# TPcape_breakout.net
KiCad netlist of a schematic drawn in Altium Designer
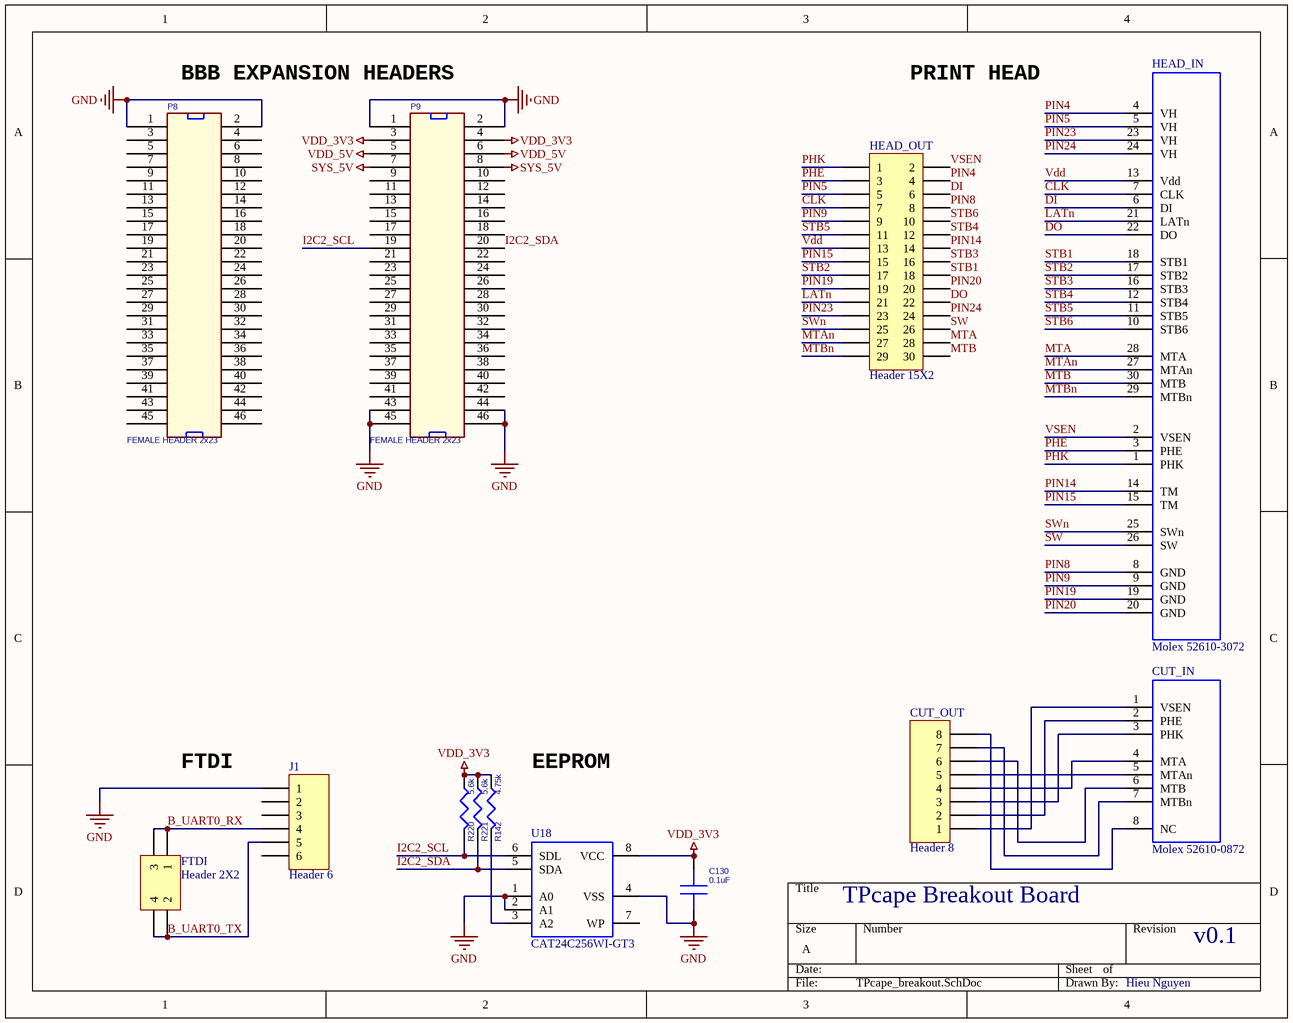
[diagram p0: TPcape_breakout.SchDoc]

(export (version "E")
  (design (tool "Eeschema 10.0.6"))
  (components
    (comp (ref "C130")
      (value "0.1uF")
      (footprint "402")
      (description "No Description")
      (libsource (lib "BEAGLEBONEBLACK_REV A5B") (part "CAP SMD"))
    )
    (comp (ref "CUT_IN")
      (value "Molex 52610-0872")
      (footprint "Molex 52610-0872")
      (description "FPC connector for Fujitsu FTP-628MCL401 (Molex 52610-0871 is obsolete)")
      (libsource (lib "AM335x_Thermal_Printer") (part "Molex 52610-0872"))
    )
    (comp (ref "CUT_OUT")
      (value "Header 8")
      (footprint "HDR1X8")
      (description "Header, 8-Pin")
      (fields (field (name "PUBLISHER") "Altium Limited"))
      (libsource (lib "Miscellaneous Connectors") (part "Header 8"))
    )
    (comp (ref "FTDI")
      (value "Header 2X2")
      (footprint "SSM-102-S-DV")
      (description "Header, 2-Pin, Dual row")
      (fields (field (name "PUBLISHER") "Altium Limited"))
      (libsource (lib "Miscellaneous Connectors") (part "Header 2X2"))
    )
    (comp (ref "HEAD_IN")
      (value "Molex 52610-3072")
      (footprint "Molex 52610-3072")
      (description "FPC connector for Fujitsu FTP-628MCL401 print head (Molex 52610-3071 is obsolete)")
      (libsource (lib "AM335x_Thermal_Printer") (part "Molex 52610-3072"))
    )
    (comp (ref "HEAD_OUT")
      (value "Header 15X2")
      (footprint "HDR2X15")
      (description "Header, 15-Pin, Dual row")
      (fields (field (name "PUBLISHER") "Altium Limited"))
      (libsource (lib "Miscellaneous Connectors") (part "Header 15X2"))
    )
    (comp (ref "J1")
      (value "Header 6")
      (footprint "HDR1X6")
      (description "Header, 6-Pin")
      (fields (field (name "PUBLISHER") "Altium Limited"))
      (libsource (lib "Miscellaneous Connectors") (part "Header 6"))
    )
    (comp (ref "P8")
      (value "FEMALE HEADER 2x23")
      (description "CONN HEADER FMAL 46PS.1\" DL GOLD")
      (fields
        (field (name "MANUFACTURER") "Sullins Connector Solutions")
        (field (name "MANUFACTURER PART NUMBER") "PPPC232LFBN-RC")
      )
      (libsource (lib "BEAGLEBONEBLACK_REV A5B") (part "HDR_46_F_2_0.1_0.1"))
    )
    (comp (ref "P9")
      (value "FEMALE HEADER 2x23")
      (description "CONN HEADER FMAL 46PS.1\" DL GOLD")
      (fields
        (field (name "MANUFACTURER") "Sullins Connector Solutions")
        (field (name "MANUFACTURER PART NUMBER") "PPPC232LFBN-RC")
      )
      (libsource (lib "BEAGLEBONEBLACK_REV A5B") (part "HDR_46_F_2_0.1_0.1"))
    )
    (comp (ref "R142")
      (value "4.75k")
      (footprint "402")
      (description "RES 5.6K OHM 1/16W 5% 0402 SMD")
      (fields
        (field (name "MANUFACTURER") "Rohm Semiconductor")
        (field (name "MANUFACTURER PART NUMBER") "MCR01MZPJ103")
      )
      (libsource (lib "BEAGLEBONEBLACK_REV A5B") (part "RES SMD"))
    )
    (comp (ref "R220")
      (value "5.6k")
      (footprint "402")
      (description "RES 5.6K OHM 1/16W 5% 0402 SMD")
      (fields
        (field (name "MANUFACTURER") "Rohm Semiconductor")
        (field (name "MANUFACTURER PART NUMBER") "MCR01MZPJ103")
      )
      (libsource (lib "BEAGLEBONEBLACK_REV A5B") (part "RES SMD"))
    )
    (comp (ref "R221")
      (value "5.6k")
      (footprint "402")
      (description "RES 5.6K OHM 1/16W 5% 0402 SMD")
      (fields
        (field (name "MANUFACTURER") "Rohm Semiconductor")
        (field (name "MANUFACTURER PART NUMBER") "MCR01MZPJ103")
      )
      (libsource (lib "BEAGLEBONEBLACK_REV A5B") (part "RES SMD"))
    )
    (comp (ref "U18")
      (value "CAT24C256WI-GT3")
      (footprint "CAT24C256WI-GT3")
      (description "IC EEPROM 256KBIT 400KHZ 8SOIC")
      (libsource (lib "AM335x_Thermal_Printer") (part "CAT24C256WI-GT3"))
    )
  )
  (nets
    (net (code "1") (name "/B_UART0_RX") (class "Default")
      (node (ref "FTDI") (pin "1") (pinfunction "1_1") (pintype "passive"))
      (node (ref "FTDI") (pin "3") (pinfunction "3_3") (pintype "passive"))
      (node (ref "J1") (pin "4") (pinfunction "4_4") (pintype "passive"))
    )
    (net (code "2") (name "/B_UART0_TX") (class "Default")
      (node (ref "FTDI") (pin "2") (pinfunction "2_2") (pintype "passive"))
      (node (ref "FTDI") (pin "4") (pinfunction "4_4") (pintype "passive"))
      (node (ref "J1") (pin "5") (pinfunction "5_5") (pintype "passive"))
    )
    (net (code "3") (name "/CLK") (class "Default")
      (node (ref "HEAD_IN") (pin "7") (pinfunction "CLK_7") (pintype "passive"))
      (node (ref "HEAD_OUT") (pin "7") (pinfunction "7_7") (pintype "passive"))
    )
    (net (code "4") (name "/DI") (class "Default")
      (node (ref "HEAD_IN") (pin "6") (pinfunction "DI_6") (pintype "passive"))
      (node (ref "HEAD_OUT") (pin "6") (pinfunction "6_6") (pintype "passive"))
    )
    (net (code "5") (name "/DO") (class "Default")
      (node (ref "HEAD_IN") (pin "22") (pinfunction "DO_22") (pintype "passive"))
      (node (ref "HEAD_OUT") (pin "22") (pinfunction "22_22") (pintype "passive"))
    )
    (net (code "6") (name "/I2C2_SCL") (class "Default")
      (node (ref "P9") (pin "19") (pinfunction "10_19") (pintype "passive"))
      (node (ref "R220") (pin "1") (pinfunction "P1_1") (pintype "passive"))
      (node (ref "U18") (pin "6") (pinfunction "SDL_6") (pintype "passive"))
    )
    (net (code "7") (name "/I2C2_SDA") (class "Default")
      (node (ref "P9") (pin "20") (pinfunction "35_20") (pintype "passive"))
      (node (ref "R221") (pin "1") (pinfunction "P1_1") (pintype "passive"))
      (node (ref "U18") (pin "5") (pinfunction "SDA_5") (pintype "passive"))
    )
    (net (code "8") (name "/LATn") (class "Default")
      (node (ref "HEAD_IN") (pin "21") (pinfunction "LATn_21") (pintype "passive"))
      (node (ref "HEAD_OUT") (pin "21") (pinfunction "21_21") (pintype "passive"))
    )
    (net (code "9") (name "/MTA") (class "Default")
      (node (ref "HEAD_IN") (pin "28") (pinfunction "MTA_28") (pintype "passive"))
      (node (ref "HEAD_OUT") (pin "28") (pinfunction "28_28") (pintype "passive"))
    )
    (net (code "10") (name "/MTAn") (class "Default")
      (node (ref "HEAD_IN") (pin "27") (pinfunction "MTAn_27") (pintype "passive"))
      (node (ref "HEAD_OUT") (pin "27") (pinfunction "27_27") (pintype "passive"))
    )
    (net (code "11") (name "/MTB") (class "Default")
      (node (ref "HEAD_IN") (pin "30") (pinfunction "MTB_30") (pintype "passive"))
      (node (ref "HEAD_OUT") (pin "30") (pinfunction "30_30") (pintype "passive"))
    )
    (net (code "12") (name "/MTBn") (class "Default")
      (node (ref "HEAD_IN") (pin "29") (pinfunction "MTBn_29") (pintype "passive"))
      (node (ref "HEAD_OUT") (pin "29") (pinfunction "29_29") (pintype "passive"))
    )
    (net (code "13") (name "/PHE") (class "Default")
      (node (ref "HEAD_IN") (pin "3") (pinfunction "PHE_3") (pintype "passive"))
      (node (ref "HEAD_OUT") (pin "3") (pinfunction "3_3") (pintype "passive"))
    )
    (net (code "14") (name "/PHK") (class "Default")
      (node (ref "HEAD_IN") (pin "1") (pinfunction "PHK_1") (pintype "passive"))
      (node (ref "HEAD_OUT") (pin "1") (pinfunction "1_1") (pintype "passive"))
    )
    (net (code "15") (name "/PIN4") (class "Default")
      (node (ref "HEAD_IN") (pin "4") (pinfunction "VH_4") (pintype "passive"))
      (node (ref "HEAD_OUT") (pin "4") (pinfunction "4_4") (pintype "passive"))
    )
    (net (code "16") (name "/PIN5") (class "Default")
      (node (ref "HEAD_IN") (pin "5") (pinfunction "VH_5") (pintype "passive"))
      (node (ref "HEAD_OUT") (pin "5") (pinfunction "5_5") (pintype "passive"))
    )
    (net (code "17") (name "/PIN8") (class "Default")
      (node (ref "HEAD_IN") (pin "8") (pinfunction "GND_8") (pintype "passive"))
      (node (ref "HEAD_OUT") (pin "8") (pinfunction "8_8") (pintype "passive"))
    )
    (net (code "18") (name "/PIN9") (class "Default")
      (node (ref "HEAD_IN") (pin "9") (pinfunction "GND_9") (pintype "passive"))
      (node (ref "HEAD_OUT") (pin "9") (pinfunction "9_9") (pintype "passive"))
    )
    (net (code "19") (name "/PIN14") (class "Default")
      (node (ref "HEAD_IN") (pin "14") (pinfunction "TM_14") (pintype "passive"))
      (node (ref "HEAD_OUT") (pin "14") (pinfunction "14_14") (pintype "passive"))
    )
    (net (code "20") (name "/PIN15") (class "Default")
      (node (ref "HEAD_IN") (pin "15") (pinfunction "TM_15") (pintype "passive"))
      (node (ref "HEAD_OUT") (pin "15") (pinfunction "15_15") (pintype "passive"))
    )
    (net (code "21") (name "/PIN19") (class "Default")
      (node (ref "HEAD_IN") (pin "19") (pinfunction "GND_19") (pintype "passive"))
      (node (ref "HEAD_OUT") (pin "19") (pinfunction "19_19") (pintype "passive"))
    )
    (net (code "22") (name "/PIN20") (class "Default")
      (node (ref "HEAD_IN") (pin "20") (pinfunction "GND_20") (pintype "passive"))
      (node (ref "HEAD_OUT") (pin "20") (pinfunction "20_20") (pintype "passive"))
    )
    (net (code "23") (name "/PIN23") (class "Default")
      (node (ref "HEAD_IN") (pin "23") (pinfunction "VH_23") (pintype "passive"))
      (node (ref "HEAD_OUT") (pin "23") (pinfunction "23_23") (pintype "passive"))
    )
    (net (code "24") (name "/PIN24") (class "Default")
      (node (ref "HEAD_IN") (pin "24") (pinfunction "VH_24") (pintype "passive"))
      (node (ref "HEAD_OUT") (pin "24") (pinfunction "24_24") (pintype "passive"))
    )
    (net (code "25") (name "/STB1") (class "Default")
      (node (ref "HEAD_IN") (pin "18") (pinfunction "STB1_18") (pintype "passive"))
      (node (ref "HEAD_OUT") (pin "18") (pinfunction "18_18") (pintype "passive"))
    )
    (net (code "26") (name "/STB2") (class "Default")
      (node (ref "HEAD_IN") (pin "17") (pinfunction "STB2_17") (pintype "passive"))
      (node (ref "HEAD_OUT") (pin "17") (pinfunction "17_17") (pintype "passive"))
    )
    (net (code "27") (name "/STB3") (class "Default")
      (node (ref "HEAD_IN") (pin "16") (pinfunction "STB3_16") (pintype "passive"))
      (node (ref "HEAD_OUT") (pin "16") (pinfunction "16_16") (pintype "passive"))
    )
    (net (code "28") (name "/STB4") (class "Default")
      (node (ref "HEAD_IN") (pin "12") (pinfunction "STB4_12") (pintype "passive"))
      (node (ref "HEAD_OUT") (pin "12") (pinfunction "12_12") (pintype "passive"))
    )
    (net (code "29") (name "/STB5") (class "Default")
      (node (ref "HEAD_IN") (pin "11") (pinfunction "STB5_11") (pintype "passive"))
      (node (ref "HEAD_OUT") (pin "11") (pinfunction "11_11") (pintype "passive"))
    )
    (net (code "30") (name "/STB6") (class "Default")
      (node (ref "HEAD_IN") (pin "10") (pinfunction "STB6_10") (pintype "passive"))
      (node (ref "HEAD_OUT") (pin "10") (pinfunction "10_10") (pintype "passive"))
    )
    (net (code "31") (name "/SW") (class "Default")
      (node (ref "HEAD_IN") (pin "26") (pinfunction "SW_26") (pintype "passive"))
      (node (ref "HEAD_OUT") (pin "26") (pinfunction "26_26") (pintype "passive"))
    )
    (net (code "32") (name "/SWn") (class "Default")
      (node (ref "HEAD_IN") (pin "25") (pinfunction "SWn_25") (pintype "passive"))
      (node (ref "HEAD_OUT") (pin "25") (pinfunction "25_25") (pintype "passive"))
    )
    (net (code "33") (name "/VSEN") (class "Default")
      (node (ref "HEAD_IN") (pin "2") (pinfunction "VSEN_2") (pintype "passive"))
      (node (ref "HEAD_OUT") (pin "2") (pinfunction "2_2") (pintype "passive"))
    )
    (net (code "34") (name "/Vdd") (class "Default")
      (node (ref "HEAD_IN") (pin "13") (pinfunction "Vdd_13") (pintype "passive"))
      (node (ref "HEAD_OUT") (pin "13") (pinfunction "13_13") (pintype "passive"))
    )
    (net (code "35") (name "GND") (class "Default")
      (node (ref "C130") (pin "2") (pinfunction "2_2") (pintype "passive"))
      (node (ref "J1") (pin "1") (pinfunction "1_1") (pintype "passive"))
      (node (ref "P8") (pin "1") (pinfunction "1_1") (pintype "passive"))
      (node (ref "P8") (pin "2") (pinfunction "26_2") (pintype "passive"))
      (node (ref "P9") (pin "1") (pinfunction "1_1") (pintype "passive"))
      (node (ref "P9") (pin "2") (pinfunction "26_2") (pintype "passive"))
      (node (ref "P9") (pin "43") (pinfunction "22_43") (pintype "passive"))
      (node (ref "P9") (pin "44") (pinfunction "47_44") (pintype "passive"))
      (node (ref "P9") (pin "45") (pinfunction "23_45") (pintype "passive"))
      (node (ref "P9") (pin "46") (pinfunction "48_46") (pintype "passive"))
      (node (ref "U18") (pin "1") (pinfunction "A0_1") (pintype "passive"))
      (node (ref "U18") (pin "2") (pinfunction "A1_2") (pintype "passive"))
      (node (ref "U18") (pin "4") (pinfunction "VSS_4") (pintype "passive"))
    )
    (net (code "36") (name "Net-(CUT_IN-MTA)") (class "Default")
      (node (ref "CUT_IN") (pin "4") (pinfunction "MTA_4") (pintype "passive"))
      (node (ref "CUT_OUT") (pin "4") (pinfunction "4_4") (pintype "passive"))
    )
    (net (code "37") (name "Net-(CUT_IN-MTAn)") (class "Default")
      (node (ref "CUT_IN") (pin "5") (pinfunction "MTAn_5") (pintype "passive"))
      (node (ref "CUT_OUT") (pin "5") (pinfunction "5_5") (pintype "passive"))
    )
    (net (code "38") (name "Net-(CUT_IN-MTB)") (class "Default")
      (node (ref "CUT_IN") (pin "6") (pinfunction "MTB_6") (pintype "passive"))
      (node (ref "CUT_OUT") (pin "6") (pinfunction "6_6") (pintype "passive"))
    )
    (net (code "39") (name "Net-(CUT_IN-MTBn)") (class "Default")
      (node (ref "CUT_IN") (pin "7") (pinfunction "MTBn_7") (pintype "passive"))
      (node (ref "CUT_OUT") (pin "7") (pinfunction "7_7") (pintype "passive"))
    )
    (net (code "40") (name "Net-(CUT_IN-NC)") (class "Default")
      (node (ref "CUT_IN") (pin "8") (pinfunction "NC_8") (pintype "passive"))
      (node (ref "CUT_OUT") (pin "8") (pinfunction "8_8") (pintype "passive"))
    )
    (net (code "41") (name "Net-(CUT_IN-PHE)") (class "Default")
      (node (ref "CUT_IN") (pin "2") (pinfunction "PHE_2") (pintype "passive"))
      (node (ref "CUT_OUT") (pin "2") (pinfunction "2_2") (pintype "passive"))
    )
    (net (code "42") (name "Net-(CUT_IN-PHK)") (class "Default")
      (node (ref "CUT_IN") (pin "3") (pinfunction "PHK_3") (pintype "passive"))
      (node (ref "CUT_OUT") (pin "3") (pinfunction "3_3") (pintype "passive"))
    )
    (net (code "43") (name "Net-(CUT_IN-VSEN)") (class "Default")
      (node (ref "CUT_IN") (pin "1") (pinfunction "VSEN_1") (pintype "passive"))
      (node (ref "CUT_OUT") (pin "1") (pinfunction "1_1") (pintype "passive"))
    )
    (net (code "44") (name "Net-(R142-P1)") (class "Default")
      (node (ref "R142") (pin "1") (pinfunction "P1_1") (pintype "passive"))
      (node (ref "U18") (pin "3") (pinfunction "A2_3") (pintype "passive"))
    )
    (net (code "45") (name "SYS_5V") (class "Default")
      (node (ref "P9") (pin "7") (pinfunction "4_7") (pintype "passive"))
      (node (ref "P9") (pin "8") (pinfunction "29_8") (pintype "passive"))
    )
    (net (code "46") (name "VDD_3V3") (class "Default")
      (node (ref "C130") (pin "1") (pinfunction "1_1") (pintype "passive"))
      (node (ref "P9") (pin "3") (pinfunction "2_3") (pintype "passive"))
      (node (ref "P9") (pin "4") (pinfunction "27_4") (pintype "passive"))
      (node (ref "R142") (pin "2") (pinfunction "P2_2") (pintype "passive"))
      (node (ref "R220") (pin "2") (pinfunction "P2_2") (pintype "passive"))
      (node (ref "R221") (pin "2") (pinfunction "P2_2") (pintype "passive"))
      (node (ref "U18") (pin "8") (pinfunction "VCC_8") (pintype "passive"))
    )
    (net (code "47") (name "VDD_5V") (class "Default")
      (node (ref "P9") (pin "5") (pinfunction "3_5") (pintype "passive"))
      (node (ref "P9") (pin "6") (pinfunction "28_6") (pintype "passive"))
    )
    (net (code "48") (name "unconnected-(J1-Pad2)") (class "Default")
      (node (ref "J1") (pin "2") (pinfunction "2_2") (pintype "passive"))
    )
    (net (code "49") (name "unconnected-(J1-Pad3)") (class "Default")
      (node (ref "J1") (pin "3") (pinfunction "3_3") (pintype "passive"))
    )
    (net (code "50") (name "unconnected-(J1-Pad6)") (class "Default")
      (node (ref "J1") (pin "6") (pinfunction "6_6") (pintype "passive"))
    )
    (net (code "51") (name "unconnected-(P8-2-Pad3)") (class "Default")
      (node (ref "P8") (pin "3") (pinfunction "2_3") (pintype "passive"))
    )
    (net (code "52") (name "unconnected-(P8-3-Pad5)") (class "Default")
      (node (ref "P8") (pin "5") (pinfunction "3_5") (pintype "passive"))
    )
    (net (code "53") (name "unconnected-(P8-4-Pad7)") (class "Default")
      (node (ref "P8") (pin "7") (pinfunction "4_7") (pintype "passive"))
    )
    (net (code "54") (name "unconnected-(P8-5-Pad9)") (class "Default")
      (node (ref "P8") (pin "9") (pinfunction "5_9") (pintype "passive"))
    )
    (net (code "55") (name "unconnected-(P8-6-Pad11)") (class "Default")
      (node (ref "P8") (pin "11") (pinfunction "6_11") (pintype "passive"))
    )
    (net (code "56") (name "unconnected-(P8-7-Pad13)") (class "Default")
      (node (ref "P8") (pin "13") (pinfunction "7_13") (pintype "passive"))
    )
    (net (code "57") (name "unconnected-(P8-8-Pad15)") (class "Default")
      (node (ref "P8") (pin "15") (pinfunction "8_15") (pintype "passive"))
    )
    (net (code "58") (name "unconnected-(P8-9-Pad17)") (class "Default")
      (node (ref "P8") (pin "17") (pinfunction "9_17") (pintype "passive"))
    )
    (net (code "59") (name "unconnected-(P8-10-Pad19)") (class "Default")
      (node (ref "P8") (pin "19") (pinfunction "10_19") (pintype "passive"))
    )
    (net (code "60") (name "unconnected-(P8-11-Pad21)") (class "Default")
      (node (ref "P8") (pin "21") (pinfunction "11_21") (pintype "passive"))
    )
    (net (code "61") (name "unconnected-(P8-12-Pad23)") (class "Default")
      (node (ref "P8") (pin "23") (pinfunction "12_23") (pintype "passive"))
    )
    (net (code "62") (name "unconnected-(P8-13-Pad25)") (class "Default")
      (node (ref "P8") (pin "25") (pinfunction "13_25") (pintype "passive"))
    )
    (net (code "63") (name "unconnected-(P8-14-Pad27)") (class "Default")
      (node (ref "P8") (pin "27") (pinfunction "14_27") (pintype "passive"))
    )
    (net (code "64") (name "unconnected-(P8-15-Pad29)") (class "Default")
      (node (ref "P8") (pin "29") (pinfunction "15_29") (pintype "passive"))
    )
    (net (code "65") (name "unconnected-(P8-16-Pad31)") (class "Default")
      (node (ref "P8") (pin "31") (pinfunction "16_31") (pintype "passive"))
    )
    (net (code "66") (name "unconnected-(P8-17-Pad33)") (class "Default")
      (node (ref "P8") (pin "33") (pinfunction "17_33") (pintype "passive"))
    )
    (net (code "67") (name "unconnected-(P8-18-Pad35)") (class "Default")
      (node (ref "P8") (pin "35") (pinfunction "18_35") (pintype "passive"))
    )
    (net (code "68") (name "unconnected-(P8-19-Pad37)") (class "Default")
      (node (ref "P8") (pin "37") (pinfunction "19_37") (pintype "passive"))
    )
    (net (code "69") (name "unconnected-(P8-20-Pad39)") (class "Default")
      (node (ref "P8") (pin "39") (pinfunction "20_39") (pintype "passive"))
    )
    (net (code "70") (name "unconnected-(P8-21-Pad41)") (class "Default")
      (node (ref "P8") (pin "41") (pinfunction "21_41") (pintype "passive"))
    )
    (net (code "71") (name "unconnected-(P8-22-Pad43)") (class "Default")
      (node (ref "P8") (pin "43") (pinfunction "22_43") (pintype "passive"))
    )
    (net (code "72") (name "unconnected-(P8-23-Pad45)") (class "Default")
      (node (ref "P8") (pin "45") (pinfunction "23_45") (pintype "passive"))
    )
    (net (code "73") (name "unconnected-(P8-27-Pad4)") (class "Default")
      (node (ref "P8") (pin "4") (pinfunction "27_4") (pintype "passive"))
    )
    (net (code "74") (name "unconnected-(P8-28-Pad6)") (class "Default")
      (node (ref "P8") (pin "6") (pinfunction "28_6") (pintype "passive"))
    )
    (net (code "75") (name "unconnected-(P8-29-Pad8)") (class "Default")
      (node (ref "P8") (pin "8") (pinfunction "29_8") (pintype "passive"))
    )
    (net (code "76") (name "unconnected-(P8-30-Pad10)") (class "Default")
      (node (ref "P8") (pin "10") (pinfunction "30_10") (pintype "passive"))
    )
    (net (code "77") (name "unconnected-(P8-31-Pad12)") (class "Default")
      (node (ref "P8") (pin "12") (pinfunction "31_12") (pintype "passive"))
    )
    (net (code "78") (name "unconnected-(P8-32-Pad14)") (class "Default")
      (node (ref "P8") (pin "14") (pinfunction "32_14") (pintype "passive"))
    )
    (net (code "79") (name "unconnected-(P8-33-Pad16)") (class "Default")
      (node (ref "P8") (pin "16") (pinfunction "33_16") (pintype "passive"))
    )
    (net (code "80") (name "unconnected-(P8-34-Pad18)") (class "Default")
      (node (ref "P8") (pin "18") (pinfunction "34_18") (pintype "passive"))
    )
    (net (code "81") (name "unconnected-(P8-35-Pad20)") (class "Default")
      (node (ref "P8") (pin "20") (pinfunction "35_20") (pintype "passive"))
    )
    (net (code "82") (name "unconnected-(P8-36-Pad22)") (class "Default")
      (node (ref "P8") (pin "22") (pinfunction "36_22") (pintype "passive"))
    )
    (net (code "83") (name "unconnected-(P8-37-Pad24)") (class "Default")
      (node (ref "P8") (pin "24") (pinfunction "37_24") (pintype "passive"))
    )
    (net (code "84") (name "unconnected-(P8-38-Pad26)") (class "Default")
      (node (ref "P8") (pin "26") (pinfunction "38_26") (pintype "passive"))
    )
    (net (code "85") (name "unconnected-(P8-39-Pad28)") (class "Default")
      (node (ref "P8") (pin "28") (pinfunction "39_28") (pintype "passive"))
    )
    (net (code "86") (name "unconnected-(P8-40-Pad30)") (class "Default")
      (node (ref "P8") (pin "30") (pinfunction "40_30") (pintype "passive"))
    )
    (net (code "87") (name "unconnected-(P8-41-Pad32)") (class "Default")
      (node (ref "P8") (pin "32") (pinfunction "41_32") (pintype "passive"))
    )
    (net (code "88") (name "unconnected-(P8-42-Pad34)") (class "Default")
      (node (ref "P8") (pin "34") (pinfunction "42_34") (pintype "passive"))
    )
    (net (code "89") (name "unconnected-(P8-43-Pad36)") (class "Default")
      (node (ref "P8") (pin "36") (pinfunction "43_36") (pintype "passive"))
    )
    (net (code "90") (name "unconnected-(P8-44-Pad38)") (class "Default")
      (node (ref "P8") (pin "38") (pinfunction "44_38") (pintype "passive"))
    )
    (net (code "91") (name "unconnected-(P8-45-Pad40)") (class "Default")
      (node (ref "P8") (pin "40") (pinfunction "45_40") (pintype "passive"))
    )
    (net (code "92") (name "unconnected-(P8-46-Pad42)") (class "Default")
      (node (ref "P8") (pin "42") (pinfunction "46_42") (pintype "passive"))
    )
    (net (code "93") (name "unconnected-(P8-47-Pad44)") (class "Default")
      (node (ref "P8") (pin "44") (pinfunction "47_44") (pintype "passive"))
    )
    (net (code "94") (name "unconnected-(P8-48-Pad46)") (class "Default")
      (node (ref "P8") (pin "46") (pinfunction "48_46") (pintype "passive"))
    )
    (net (code "95") (name "unconnected-(P9-5-Pad9)") (class "Default")
      (node (ref "P9") (pin "9") (pinfunction "5_9") (pintype "passive"))
    )
    (net (code "96") (name "unconnected-(P9-6-Pad11)") (class "Default")
      (node (ref "P9") (pin "11") (pinfunction "6_11") (pintype "passive"))
    )
    (net (code "97") (name "unconnected-(P9-7-Pad13)") (class "Default")
      (node (ref "P9") (pin "13") (pinfunction "7_13") (pintype "passive"))
    )
    (net (code "98") (name "unconnected-(P9-8-Pad15)") (class "Default")
      (node (ref "P9") (pin "15") (pinfunction "8_15") (pintype "passive"))
    )
    (net (code "99") (name "unconnected-(P9-9-Pad17)") (class "Default")
      (node (ref "P9") (pin "17") (pinfunction "9_17") (pintype "passive"))
    )
    (net (code "100") (name "unconnected-(P9-11-Pad21)") (class "Default")
      (node (ref "P9") (pin "21") (pinfunction "11_21") (pintype "passive"))
    )
    (net (code "101") (name "unconnected-(P9-12-Pad23)") (class "Default")
      (node (ref "P9") (pin "23") (pinfunction "12_23") (pintype "passive"))
    )
    (net (code "102") (name "unconnected-(P9-13-Pad25)") (class "Default")
      (node (ref "P9") (pin "25") (pinfunction "13_25") (pintype "passive"))
    )
    (net (code "103") (name "unconnected-(P9-14-Pad27)") (class "Default")
      (node (ref "P9") (pin "27") (pinfunction "14_27") (pintype "passive"))
    )
    (net (code "104") (name "unconnected-(P9-15-Pad29)") (class "Default")
      (node (ref "P9") (pin "29") (pinfunction "15_29") (pintype "passive"))
    )
    (net (code "105") (name "unconnected-(P9-16-Pad31)") (class "Default")
      (node (ref "P9") (pin "31") (pinfunction "16_31") (pintype "passive"))
    )
    (net (code "106") (name "unconnected-(P9-17-Pad33)") (class "Default")
      (node (ref "P9") (pin "33") (pinfunction "17_33") (pintype "passive"))
    )
    (net (code "107") (name "unconnected-(P9-18-Pad35)") (class "Default")
      (node (ref "P9") (pin "35") (pinfunction "18_35") (pintype "passive"))
    )
    (net (code "108") (name "unconnected-(P9-19-Pad37)") (class "Default")
      (node (ref "P9") (pin "37") (pinfunction "19_37") (pintype "passive"))
    )
    (net (code "109") (name "unconnected-(P9-20-Pad39)") (class "Default")
      (node (ref "P9") (pin "39") (pinfunction "20_39") (pintype "passive"))
    )
    (net (code "110") (name "unconnected-(P9-21-Pad41)") (class "Default")
      (node (ref "P9") (pin "41") (pinfunction "21_41") (pintype "passive"))
    )
    (net (code "111") (name "unconnected-(P9-30-Pad10)") (class "Default")
      (node (ref "P9") (pin "10") (pinfunction "30_10") (pintype "passive"))
    )
    (net (code "112") (name "unconnected-(P9-31-Pad12)") (class "Default")
      (node (ref "P9") (pin "12") (pinfunction "31_12") (pintype "passive"))
    )
    (net (code "113") (name "unconnected-(P9-32-Pad14)") (class "Default")
      (node (ref "P9") (pin "14") (pinfunction "32_14") (pintype "passive"))
    )
    (net (code "114") (name "unconnected-(P9-33-Pad16)") (class "Default")
      (node (ref "P9") (pin "16") (pinfunction "33_16") (pintype "passive"))
    )
    (net (code "115") (name "unconnected-(P9-34-Pad18)") (class "Default")
      (node (ref "P9") (pin "18") (pinfunction "34_18") (pintype "passive"))
    )
    (net (code "116") (name "unconnected-(P9-36-Pad22)") (class "Default")
      (node (ref "P9") (pin "22") (pinfunction "36_22") (pintype "passive"))
    )
    (net (code "117") (name "unconnected-(P9-37-Pad24)") (class "Default")
      (node (ref "P9") (pin "24") (pinfunction "37_24") (pintype "passive"))
    )
    (net (code "118") (name "unconnected-(P9-38-Pad26)") (class "Default")
      (node (ref "P9") (pin "26") (pinfunction "38_26") (pintype "passive"))
    )
    (net (code "119") (name "unconnected-(P9-39-Pad28)") (class "Default")
      (node (ref "P9") (pin "28") (pinfunction "39_28") (pintype "passive"))
    )
    (net (code "120") (name "unconnected-(P9-40-Pad30)") (class "Default")
      (node (ref "P9") (pin "30") (pinfunction "40_30") (pintype "passive"))
    )
    (net (code "121") (name "unconnected-(P9-41-Pad32)") (class "Default")
      (node (ref "P9") (pin "32") (pinfunction "41_32") (pintype "passive"))
    )
    (net (code "122") (name "unconnected-(P9-42-Pad34)") (class "Default")
      (node (ref "P9") (pin "34") (pinfunction "42_34") (pintype "passive"))
    )
    (net (code "123") (name "unconnected-(P9-43-Pad36)") (class "Default")
      (node (ref "P9") (pin "36") (pinfunction "43_36") (pintype "passive"))
    )
    (net (code "124") (name "unconnected-(P9-44-Pad38)") (class "Default")
      (node (ref "P9") (pin "38") (pinfunction "44_38") (pintype "passive"))
    )
    (net (code "125") (name "unconnected-(P9-45-Pad40)") (class "Default")
      (node (ref "P9") (pin "40") (pinfunction "45_40") (pintype "passive"))
    )
    (net (code "126") (name "unconnected-(P9-46-Pad42)") (class "Default")
      (node (ref "P9") (pin "42") (pinfunction "46_42") (pintype "passive"))
    )
    (net (code "127") (name "unconnected-(U18-WP-Pad7)") (class "Default")
      (node (ref "U18") (pin "7") (pinfunction "WP_7") (pintype "passive"))
    )
  )
)
